# esquema.net
KiCad netlist of a schematic drawn in EAGLE
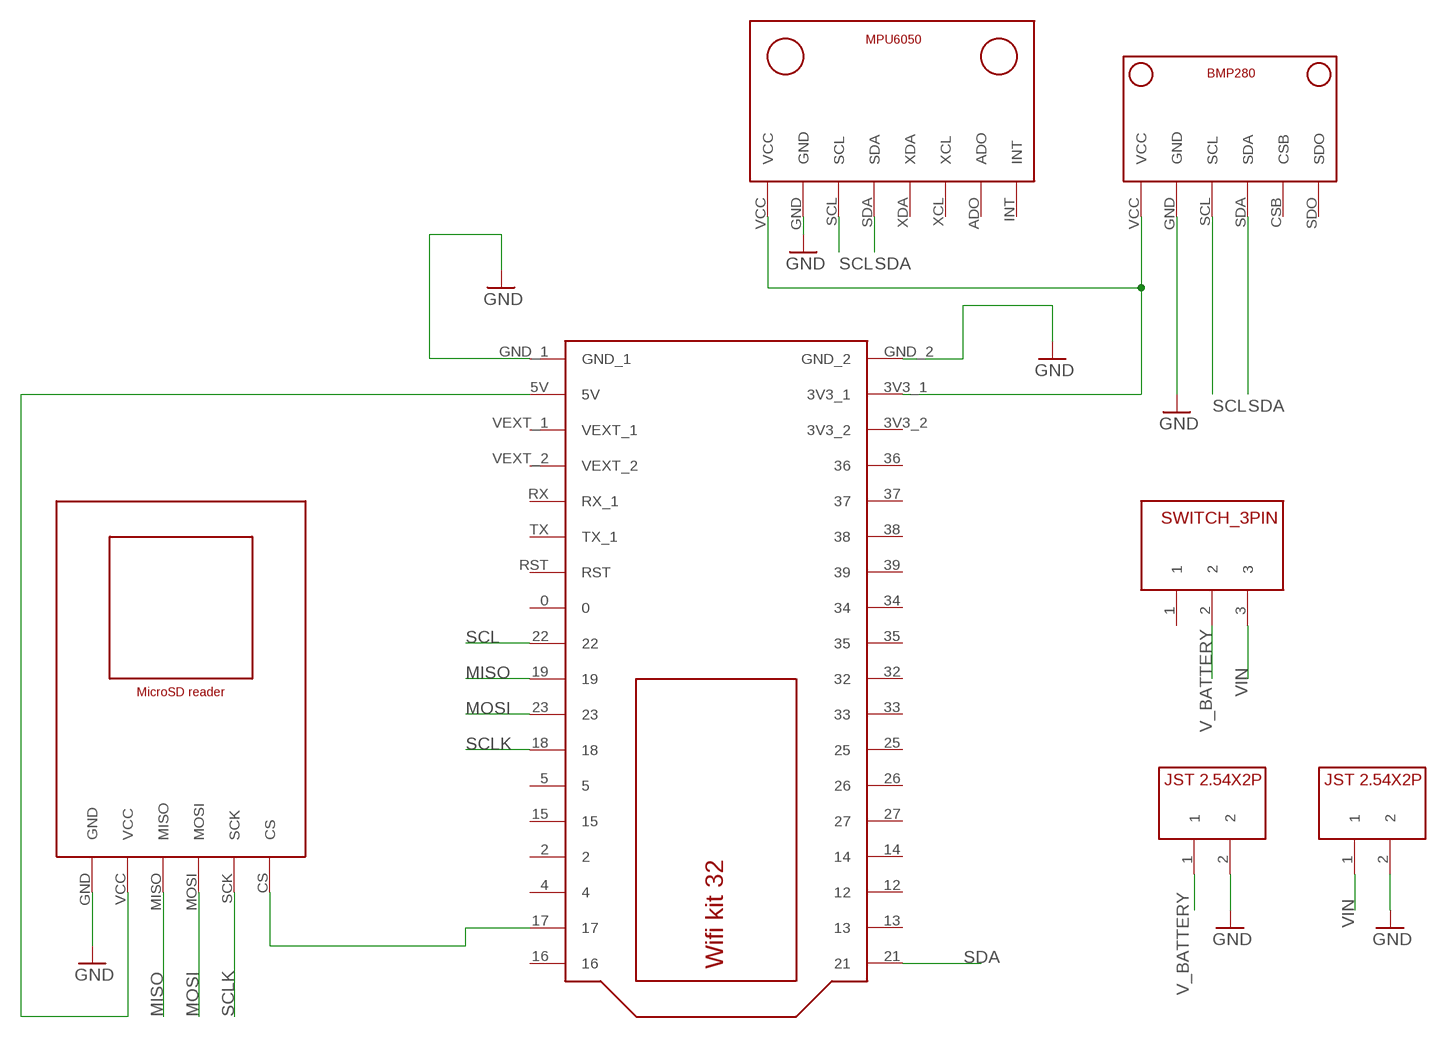
[diagram p0: schematic, sheet 1]

(export (version "E")
  (design (tool "Eeschema 10.0.6"))
  (components
    (comp (ref "U$1")
      (value "BMP280V1")
      (footprint "eagle-import:BMP280_FOOTPRINT")
      (libsource (lib "eagle-import") (part "BMP280V1"))
    )
    (comp (ref "U$2")
      (value "MICROSD_READER")
      (footprint "eagle-import:MICROSD_READER_FOOTPRINT")
      (libsource (lib "eagle-import") (part "MICROSD_READER"))
    )
    (comp (ref "U$3")
      (value "MPU6050V1")
      (footprint "eagle-import:MPU6050_FOOTPRINT")
      (libsource (lib "eagle-import") (part "MPU6050V1"))
    )
    (comp (ref "U$4")
      (value "WIFI_KIT32")
      (footprint "eagle-import:WIFI_KIT32")
      (libsource (lib "eagle-import") (part "WIFI_KIT32"))
    )
    (comp (ref "U$5")
      (value "JST2.54X2P")
      (footprint "eagle-import:JST2.54X2P_FOOTPRINT")
      (libsource (lib "eagle-import") (part "JST2.54X2P"))
    )
    (comp (ref "U$6")
      (value "SWITCH_3PIN")
      (footprint "eagle-import:SWITCH_3PIN")
      (libsource (lib "eagle-import") (part "SWITCH_3PIN"))
    )
    (comp (ref "U$7")
      (value "JST2.54X2P")
      (footprint "eagle-import:JST2.54X2P_FOOTPRINT")
      (libsource (lib "eagle-import") (part "JST2.54X2P"))
    )
  )
  (nets
    (net (code "1") (name "/MISO") (class "Default")
      (node (ref "U$2") (pin "MISO") (pinfunction "MISO_MISO") (pintype "bidirectional"))
      (node (ref "U$4") (pin "19") (pinfunction "19_19") (pintype "bidirectional"))
    )
    (net (code "2") (name "/MOSI") (class "Default")
      (node (ref "U$2") (pin "MOSI") (pinfunction "MOSI_MOSI") (pintype "bidirectional"))
      (node (ref "U$4") (pin "23") (pinfunction "23_23") (pintype "bidirectional"))
    )
    (net (code "3") (name "/SCL") (class "Default")
      (node (ref "U$1") (pin "SCL") (pinfunction "SCL_SCL") (pintype "bidirectional"))
      (node (ref "U$3") (pin "SCL") (pinfunction "SCL_SCL") (pintype "bidirectional"))
      (node (ref "U$4") (pin "22") (pinfunction "22_22") (pintype "bidirectional"))
    )
    (net (code "4") (name "/SCLK") (class "Default")
      (node (ref "U$2") (pin "SCK") (pinfunction "SCK_SCK") (pintype "bidirectional"))
      (node (ref "U$4") (pin "18") (pinfunction "18_18") (pintype "bidirectional"))
    )
    (net (code "5") (name "/SDA") (class "Default")
      (node (ref "U$1") (pin "SDA") (pinfunction "SDA_SDA") (pintype "bidirectional"))
      (node (ref "U$3") (pin "SDA") (pinfunction "SDA_SDA") (pintype "bidirectional"))
      (node (ref "U$4") (pin "21") (pinfunction "21_21") (pintype "bidirectional"))
    )
    (net (code "6") (name "/VIN") (class "Default")
      (node (ref "U$6") (pin "3") (pinfunction "3_3") (pintype "bidirectional"))
      (node (ref "U$7") (pin "1") (pinfunction "1_1") (pintype "bidirectional"))
    )
    (net (code "7") (name "/V_BATTERY") (class "Default")
      (node (ref "U$5") (pin "1") (pinfunction "1_1") (pintype "bidirectional"))
      (node (ref "U$6") (pin "2") (pinfunction "2_2") (pintype "bidirectional"))
    )
    (net (code "8") (name "GND") (class "Default")
      (node (ref "U$1") (pin "GND") (pinfunction "GND_GND") (pintype "bidirectional"))
      (node (ref "U$2") (pin "GND") (pinfunction "GND_GND") (pintype "bidirectional"))
      (node (ref "U$3") (pin "GND") (pinfunction "GND_GND") (pintype "bidirectional"))
      (node (ref "U$4") (pin "GND_1") (pinfunction "GND_1_GND_1") (pintype "bidirectional"))
      (node (ref "U$4") (pin "GND_2") (pinfunction "GND_2_GND_2") (pintype "bidirectional"))
      (node (ref "U$5") (pin "2") (pinfunction "2_2") (pintype "bidirectional"))
      (node (ref "U$7") (pin "2") (pinfunction "2_2") (pintype "bidirectional"))
    )
    (net (code "9") (name "Net-(U$1-PadVCC)") (class "Default")
      (node (ref "U$1") (pin "VCC") (pinfunction "VCC_VCC") (pintype "bidirectional"))
      (node (ref "U$3") (pin "VCC") (pinfunction "VCC_VCC") (pintype "bidirectional"))
      (node (ref "U$4") (pin "3V3_1") (pinfunction "3V3_1_3V3_1") (pintype "bidirectional"))
    )
    (net (code "10") (name "Net-(U$2-PadCS)") (class "Default")
      (node (ref "U$2") (pin "CS") (pinfunction "CS_CS") (pintype "bidirectional"))
      (node (ref "U$4") (pin "17") (pinfunction "17_17") (pintype "bidirectional"))
    )
    (net (code "11") (name "Net-(U$2-PadVCC)") (class "Default")
      (node (ref "U$2") (pin "VCC") (pinfunction "VCC_VCC") (pintype "bidirectional"))
      (node (ref "U$4") (pin "5V") (pinfunction "5V_5V") (pintype "bidirectional"))
    )
    (net (code "12") (name "unconnected-(U$1-PadCSB)") (class "Default")
      (node (ref "U$1") (pin "CSB") (pinfunction "CSB_CSB") (pintype "bidirectional"))
    )
    (net (code "13") (name "unconnected-(U$1-PadSDO)") (class "Default")
      (node (ref "U$1") (pin "SDO") (pinfunction "SDO_SDO") (pintype "bidirectional"))
    )
    (net (code "14") (name "unconnected-(U$3-PadADO)") (class "Default")
      (node (ref "U$3") (pin "ADO") (pinfunction "ADO_ADO") (pintype "bidirectional"))
    )
    (net (code "15") (name "unconnected-(U$3-PadINT)") (class "Default")
      (node (ref "U$3") (pin "INT") (pinfunction "INT_INT") (pintype "bidirectional"))
    )
    (net (code "16") (name "unconnected-(U$3-PadXCL)") (class "Default")
      (node (ref "U$3") (pin "XCL") (pinfunction "XCL_XCL") (pintype "bidirectional"))
    )
    (net (code "17") (name "unconnected-(U$3-PadXDA)") (class "Default")
      (node (ref "U$3") (pin "XDA") (pinfunction "XDA_XDA") (pintype "bidirectional"))
    )
    (net (code "18") (name "unconnected-(U$4-Pad0)") (class "Default")
      (node (ref "U$4") (pin "0") (pinfunction "0_0") (pintype "bidirectional"))
    )
    (net (code "19") (name "unconnected-(U$4-Pad2)") (class "Default")
      (node (ref "U$4") (pin "2") (pinfunction "2_2") (pintype "bidirectional"))
    )
    (net (code "20") (name "unconnected-(U$4-Pad3V3_2)") (class "Default")
      (node (ref "U$4") (pin "3V3_2") (pinfunction "3V3_2_3V3_2") (pintype "bidirectional"))
    )
    (net (code "21") (name "unconnected-(U$4-Pad4)") (class "Default")
      (node (ref "U$4") (pin "4") (pinfunction "4_4") (pintype "bidirectional"))
    )
    (net (code "22") (name "unconnected-(U$4-Pad5)") (class "Default")
      (node (ref "U$4") (pin "5") (pinfunction "5_5") (pintype "bidirectional"))
    )
    (net (code "23") (name "unconnected-(U$4-Pad12)") (class "Default")
      (node (ref "U$4") (pin "12") (pinfunction "12_12") (pintype "bidirectional"))
    )
    (net (code "24") (name "unconnected-(U$4-Pad13)") (class "Default")
      (node (ref "U$4") (pin "13") (pinfunction "13_13") (pintype "bidirectional"))
    )
    (net (code "25") (name "unconnected-(U$4-Pad14)") (class "Default")
      (node (ref "U$4") (pin "14") (pinfunction "14_14") (pintype "bidirectional"))
    )
    (net (code "26") (name "unconnected-(U$4-Pad15)") (class "Default")
      (node (ref "U$4") (pin "15") (pinfunction "15_15") (pintype "bidirectional"))
    )
    (net (code "27") (name "unconnected-(U$4-Pad16)") (class "Default")
      (node (ref "U$4") (pin "16") (pinfunction "16_16") (pintype "bidirectional"))
    )
    (net (code "28") (name "unconnected-(U$4-Pad25)") (class "Default")
      (node (ref "U$4") (pin "25") (pinfunction "25_25") (pintype "bidirectional"))
    )
    (net (code "29") (name "unconnected-(U$4-Pad26)") (class "Default")
      (node (ref "U$4") (pin "26") (pinfunction "26_26") (pintype "bidirectional"))
    )
    (net (code "30") (name "unconnected-(U$4-Pad27)") (class "Default")
      (node (ref "U$4") (pin "27") (pinfunction "27_27") (pintype "bidirectional"))
    )
    (net (code "31") (name "unconnected-(U$4-Pad32)") (class "Default")
      (node (ref "U$4") (pin "32") (pinfunction "32_32") (pintype "bidirectional"))
    )
    (net (code "32") (name "unconnected-(U$4-Pad33)") (class "Default")
      (node (ref "U$4") (pin "33") (pinfunction "33_33") (pintype "bidirectional"))
    )
    (net (code "33") (name "unconnected-(U$4-Pad34)") (class "Default")
      (node (ref "U$4") (pin "34") (pinfunction "34_34") (pintype "bidirectional"))
    )
    (net (code "34") (name "unconnected-(U$4-Pad35)") (class "Default")
      (node (ref "U$4") (pin "35") (pinfunction "35_35") (pintype "bidirectional"))
    )
    (net (code "35") (name "unconnected-(U$4-Pad36)") (class "Default")
      (node (ref "U$4") (pin "36") (pinfunction "36_36") (pintype "bidirectional"))
    )
    (net (code "36") (name "unconnected-(U$4-Pad37)") (class "Default")
      (node (ref "U$4") (pin "37") (pinfunction "37_37") (pintype "bidirectional"))
    )
    (net (code "37") (name "unconnected-(U$4-Pad38)") (class "Default")
      (node (ref "U$4") (pin "38") (pinfunction "38_38") (pintype "bidirectional"))
    )
    (net (code "38") (name "unconnected-(U$4-Pad39)") (class "Default")
      (node (ref "U$4") (pin "39") (pinfunction "39_39") (pintype "bidirectional"))
    )
    (net (code "39") (name "unconnected-(U$4-PadRST)") (class "Default")
      (node (ref "U$4") (pin "RST") (pinfunction "RST_RST") (pintype "bidirectional"))
    )
    (net (code "40") (name "unconnected-(U$4-PadVEXT_1)") (class "Default")
      (node (ref "U$4") (pin "VEXT_1") (pinfunction "VEXT_1_VEXT_1") (pintype "bidirectional"))
    )
    (net (code "41") (name "unconnected-(U$4-PadVEXT_2)") (class "Default")
      (node (ref "U$4") (pin "VEXT_2") (pinfunction "VEXT_2_VEXT_2") (pintype "bidirectional"))
    )
    (net (code "42") (name "unconnected-(U$4-RX_1-PadRX)") (class "Default")
      (node (ref "U$4") (pin "RX") (pinfunction "RX_1_RX") (pintype "bidirectional"))
    )
    (net (code "43") (name "unconnected-(U$4-TX_1-PadTX)") (class "Default")
      (node (ref "U$4") (pin "TX") (pinfunction "TX_1_TX") (pintype "bidirectional"))
    )
    (net (code "44") (name "unconnected-(U$6-Pad1)") (class "Default")
      (node (ref "U$6") (pin "1") (pinfunction "1_1") (pintype "bidirectional"))
    )
  )
)
